# conveyor-pcb.net
KiCad netlist of a schematic drawn in EAGLE
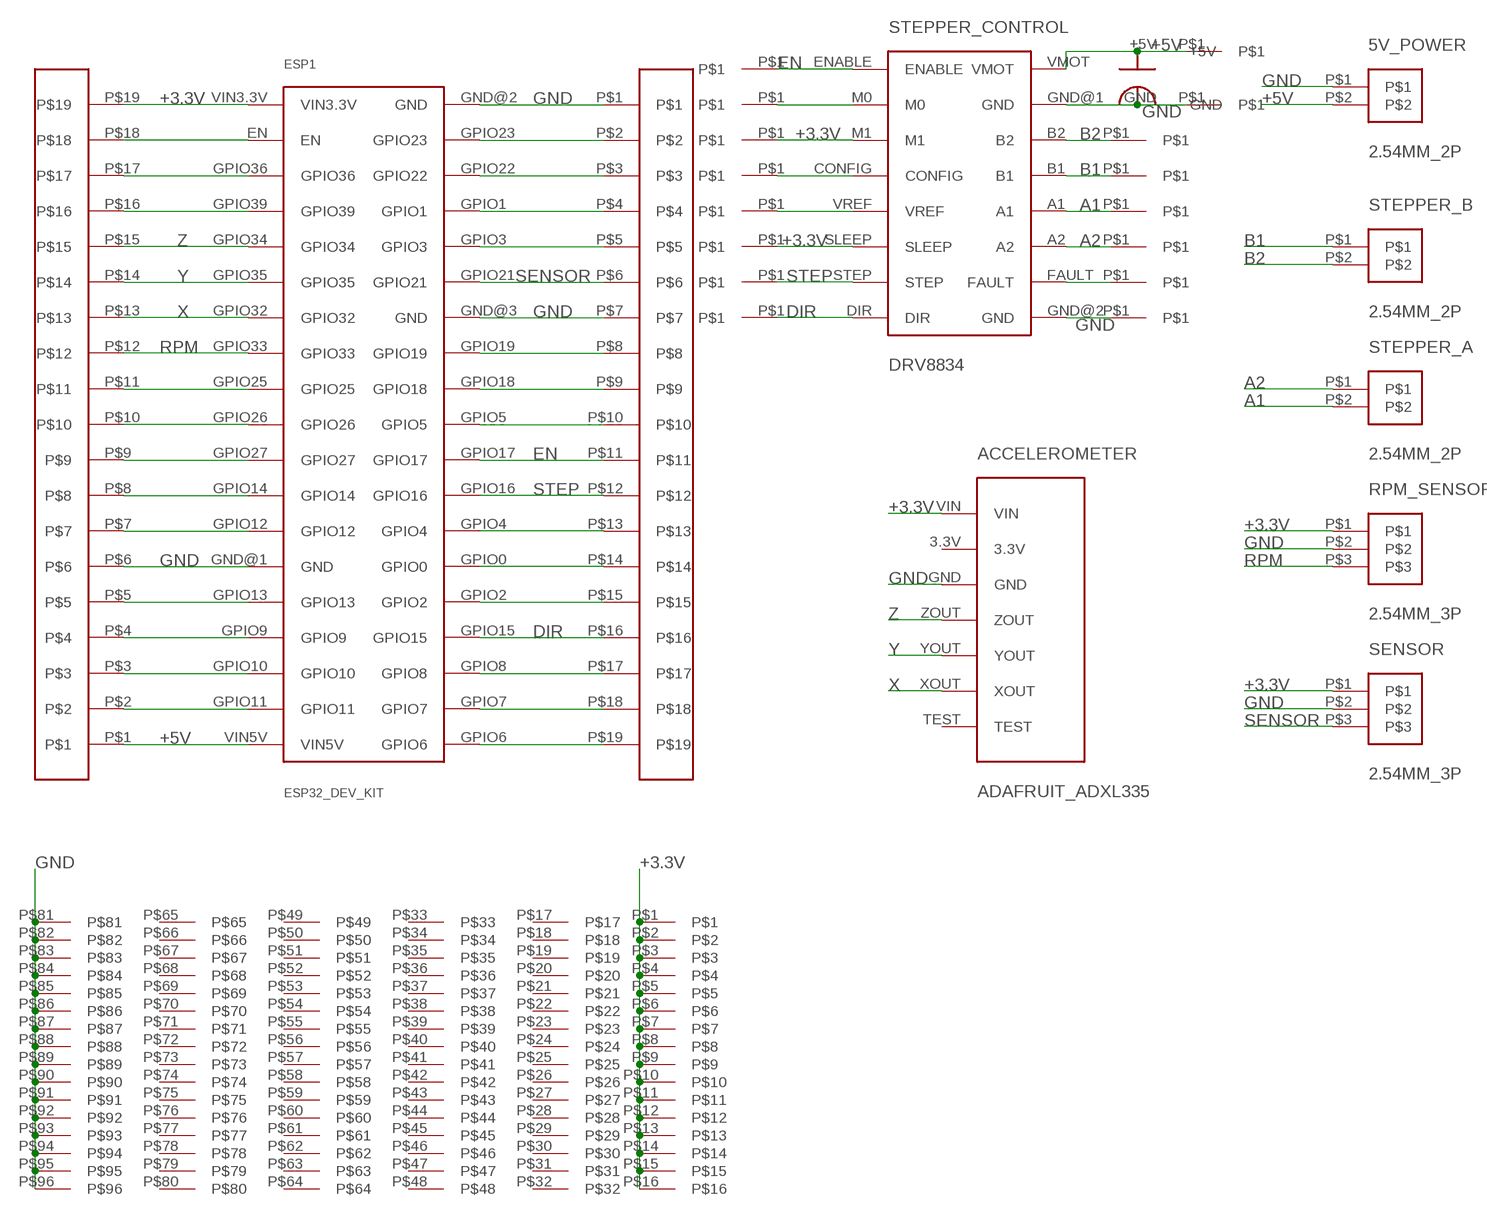
[diagram p0: schematic, sheet 1]

(export (version "E")
  (design (tool "Eeschema 10.0.6"))
  (components
    (comp (ref "5V_POWER")
      (value "2.54MM_2P")
      (footprint "eagle-import:2.54MM_2P")
      (libsource (lib "eagle-import") (part "2.54MM_2P"))
    )
    (comp (ref "ACCELEROMETER")
      (value "ADAFRUIT_ADXL335")
      (footprint "eagle-import:ADAFRUIT_ADXL335")
      (libsource (lib "eagle-import") (part "ADAFRUIT_ADXL335"))
    )
    (comp (ref "ESP1")
      (value "ESP32_DEV_KIT")
      (footprint "eagle-import:ESP32_DEV_KIT")
      (libsource (lib "eagle-import") (part "ESP32_DEV_KIT"))
    )
    (comp (ref "RPM_SENSOR")
      (value "2.54MM_3P")
      (footprint "eagle-import:2.54MM_3P")
      (libsource (lib "eagle-import") (part "2.54MM_3P"))
    )
    (comp (ref "SENSOR")
      (value "2.54MM_3P")
      (footprint "eagle-import:2.54MM_3P")
      (libsource (lib "eagle-import") (part "2.54MM_3P"))
    )
    (comp (ref "STEPPER_A")
      (value "2.54MM_2P")
      (footprint "eagle-import:2.54MM_2P")
      (libsource (lib "eagle-import") (part "2.54MM_2P"))
    )
    (comp (ref "STEPPER_B")
      (value "2.54MM_2P")
      (footprint "eagle-import:2.54MM_2P")
      (libsource (lib "eagle-import") (part "2.54MM_2P"))
    )
    (comp (ref "STEPPER_CONTROL")
      (value "DRV8834")
      (footprint "eagle-import:DRV8834")
      (libsource (lib "eagle-import") (part "DRV8834"))
    )
    (comp (ref "U$1")
      (value "19PINHEADER")
      (footprint "eagle-import:19PINHEADER")
      (libsource (lib "eagle-import") (part "19PINHEADER"))
    )
    (comp (ref "U$2")
      (value "19PINHEADER")
      (footprint "eagle-import:19PINHEADER")
      (libsource (lib "eagle-import") (part "19PINHEADER"))
    )
    (comp (ref "U$3")
      (value "PERFBOARD_CONVEYOR")
      (footprint "eagle-import:PERFBOARD_CONVEYOR")
      (libsource (lib "eagle-import") (part "PERFBOARD_CONVEYOR"))
    )
    (comp (ref "U$4")
      (value "1PIN_HEADER")
      (footprint "eagle-import:1PIN_HEADER")
      (libsource (lib "eagle-import") (part "1PIN_HEADER"))
    )
    (comp (ref "U$5")
      (value "1PIN_HEADER")
      (footprint "eagle-import:1PIN_HEADER")
      (libsource (lib "eagle-import") (part "1PIN_HEADER"))
    )
    (comp (ref "U$6")
      (value "1PIN_HEADER")
      (footprint "eagle-import:1PIN_HEADER")
      (libsource (lib "eagle-import") (part "1PIN_HEADER"))
    )
    (comp (ref "U$7")
      (value "1PIN_HEADER")
      (footprint "eagle-import:1PIN_HEADER")
      (libsource (lib "eagle-import") (part "1PIN_HEADER"))
    )
    (comp (ref "U$8")
      (value "1PIN_HEADER")
      (footprint "eagle-import:1PIN_HEADER")
      (libsource (lib "eagle-import") (part "1PIN_HEADER"))
    )
    (comp (ref "U$9")
      (value "1PIN_HEADER")
      (footprint "eagle-import:1PIN_HEADER")
      (libsource (lib "eagle-import") (part "1PIN_HEADER"))
    )
    (comp (ref "U$10")
      (value "1PIN_HEADER")
      (footprint "eagle-import:1PIN_HEADER")
      (libsource (lib "eagle-import") (part "1PIN_HEADER"))
    )
    (comp (ref "U$11")
      (value "1PIN_HEADER")
      (footprint "eagle-import:1PIN_HEADER")
      (libsource (lib "eagle-import") (part "1PIN_HEADER"))
    )
    (comp (ref "U$12")
      (value "1PIN_HEADER")
      (footprint "eagle-import:1PIN_HEADER")
      (libsource (lib "eagle-import") (part "1PIN_HEADER"))
    )
    (comp (ref "U$13")
      (value "1PIN_HEADER")
      (footprint "eagle-import:1PIN_HEADER")
      (libsource (lib "eagle-import") (part "1PIN_HEADER"))
    )
    (comp (ref "U$14")
      (value "1PIN_HEADER")
      (footprint "eagle-import:1PIN_HEADER")
      (libsource (lib "eagle-import") (part "1PIN_HEADER"))
    )
    (comp (ref "U$15")
      (value "1PIN_HEADER")
      (footprint "eagle-import:1PIN_HEADER")
      (libsource (lib "eagle-import") (part "1PIN_HEADER"))
    )
    (comp (ref "U$16")
      (value "1PIN_HEADER")
      (footprint "eagle-import:1PIN_HEADER")
      (libsource (lib "eagle-import") (part "1PIN_HEADER"))
    )
    (comp (ref "U$17")
      (value "1PIN_HEADER")
      (footprint "eagle-import:1PIN_HEADER")
      (libsource (lib "eagle-import") (part "1PIN_HEADER"))
    )
    (comp (ref "U$18")
      (value "1PIN_HEADER")
      (footprint "eagle-import:1PIN_HEADER")
      (libsource (lib "eagle-import") (part "1PIN_HEADER"))
    )
    (comp (ref "U$19")
      (value "1PIN_HEADER")
      (footprint "eagle-import:1PIN_HEADER")
      (libsource (lib "eagle-import") (part "1PIN_HEADER"))
    )
    (comp (ref "U$20")
      (value "CAP_100UF")
      (footprint "eagle-import:CAP_100UF")
      (libsource (lib "eagle-import") (part "CAP_100UF"))
    )
  )
  (nets
    (net (code "1") (name "/+3.3V") (class "Default")
      (node (ref "ACCELEROMETER") (pin "VIN") (pinfunction "VIN_VIN") (pintype "bidirectional"))
      (node (ref "ESP1") (pin "VIN3.3V") (pinfunction "VIN3.3V_VIN3.3V") (pintype "bidirectional"))
      (node (ref "RPM_SENSOR") (pin "P$1") (pinfunction "P$1_P$1") (pintype "bidirectional"))
      (node (ref "SENSOR") (pin "P$1") (pinfunction "P$1_P$1") (pintype "bidirectional"))
      (node (ref "STEPPER_CONTROL") (pin "M1") (pinfunction "M1_M1") (pintype "bidirectional"))
      (node (ref "STEPPER_CONTROL") (pin "SLEEP") (pinfunction "SLEEP_SLEEP") (pintype "bidirectional"))
      (node (ref "U$2") (pin "P$19") (pinfunction "P$19_P$19") (pintype "bidirectional"))
      (node (ref "U$3") (pin "P$1") (pinfunction "P$1_P$1") (pintype "bidirectional"))
      (node (ref "U$3") (pin "P$10") (pinfunction "P$10_P$10") (pintype "bidirectional"))
      (node (ref "U$3") (pin "P$11") (pinfunction "P$11_P$11") (pintype "bidirectional"))
      (node (ref "U$3") (pin "P$12") (pinfunction "P$12_P$12") (pintype "bidirectional"))
      (node (ref "U$3") (pin "P$13") (pinfunction "P$13_P$13") (pintype "bidirectional"))
      (node (ref "U$3") (pin "P$14") (pinfunction "P$14_P$14") (pintype "bidirectional"))
      (node (ref "U$3") (pin "P$15") (pinfunction "P$15_P$15") (pintype "bidirectional"))
      (node (ref "U$3") (pin "P$16") (pinfunction "P$16_P$16") (pintype "bidirectional"))
      (node (ref "U$3") (pin "P$2") (pinfunction "P$2_P$2") (pintype "bidirectional"))
      (node (ref "U$3") (pin "P$3") (pinfunction "P$3_P$3") (pintype "bidirectional"))
      (node (ref "U$3") (pin "P$4") (pinfunction "P$4_P$4") (pintype "bidirectional"))
      (node (ref "U$3") (pin "P$5") (pinfunction "P$5_P$5") (pintype "bidirectional"))
      (node (ref "U$3") (pin "P$6") (pinfunction "P$6_P$6") (pintype "bidirectional"))
      (node (ref "U$3") (pin "P$7") (pinfunction "P$7_P$7") (pintype "bidirectional"))
      (node (ref "U$3") (pin "P$8") (pinfunction "P$8_P$8") (pintype "bidirectional"))
      (node (ref "U$3") (pin "P$9") (pinfunction "P$9_P$9") (pintype "bidirectional"))
      (node (ref "U$6") (pin "P$1") (pinfunction "P$1_P$1") (pintype "bidirectional"))
      (node (ref "U$9") (pin "P$1") (pinfunction "P$1_P$1") (pintype "bidirectional"))
    )
    (net (code "2") (name "/+5V") (class "Default")
      (node (ref "5V_POWER") (pin "P$2") (pinfunction "P$2_P$2") (pintype "bidirectional"))
      (node (ref "ESP1") (pin "VIN5V") (pinfunction "VIN5V_VIN5V") (pintype "bidirectional"))
      (node (ref "STEPPER_CONTROL") (pin "VMOT") (pinfunction "VMOT_VMOT") (pintype "bidirectional"))
      (node (ref "U$19") (pin "P$1") (pinfunction "P$1_P$1") (pintype "bidirectional"))
      (node (ref "U$2") (pin "P$1") (pinfunction "P$1_P$1") (pintype "bidirectional"))
      (node (ref "U$20") (pin "+5V") (pinfunction "+5V_+5V") (pintype "bidirectional"))
    )
    (net (code "3") (name "/A1") (class "Default")
      (node (ref "STEPPER_A") (pin "P$2") (pinfunction "P$2_P$2") (pintype "bidirectional"))
      (node (ref "STEPPER_CONTROL") (pin "A1") (pinfunction "A1_A1") (pintype "bidirectional"))
      (node (ref "U$15") (pin "P$1") (pinfunction "P$1_P$1") (pintype "bidirectional"))
    )
    (net (code "4") (name "/A2") (class "Default")
      (node (ref "STEPPER_A") (pin "P$1") (pinfunction "P$1_P$1") (pintype "bidirectional"))
      (node (ref "STEPPER_CONTROL") (pin "A2") (pinfunction "A2_A2") (pintype "bidirectional"))
      (node (ref "U$14") (pin "P$1") (pinfunction "P$1_P$1") (pintype "bidirectional"))
    )
    (net (code "5") (name "/B1") (class "Default")
      (node (ref "STEPPER_B") (pin "P$1") (pinfunction "P$1_P$1") (pintype "bidirectional"))
      (node (ref "STEPPER_CONTROL") (pin "B1") (pinfunction "B1_B1") (pintype "bidirectional"))
      (node (ref "U$16") (pin "P$1") (pinfunction "P$1_P$1") (pintype "bidirectional"))
    )
    (net (code "6") (name "/B2") (class "Default")
      (node (ref "STEPPER_B") (pin "P$2") (pinfunction "P$2_P$2") (pintype "bidirectional"))
      (node (ref "STEPPER_CONTROL") (pin "B2") (pinfunction "B2_B2") (pintype "bidirectional"))
      (node (ref "U$17") (pin "P$1") (pinfunction "P$1_P$1") (pintype "bidirectional"))
    )
    (net (code "7") (name "/DIR") (class "Default")
      (node (ref "ESP1") (pin "GPIO15") (pinfunction "GPIO15_GPIO15") (pintype "bidirectional"))
      (node (ref "STEPPER_CONTROL") (pin "DIR") (pinfunction "DIR_DIR") (pintype "bidirectional"))
      (node (ref "U$1") (pin "P$16") (pinfunction "P$16_P$16") (pintype "bidirectional"))
      (node (ref "U$11") (pin "P$1") (pinfunction "P$1_P$1") (pintype "bidirectional"))
    )
    (net (code "8") (name "/EN") (class "Default")
      (node (ref "ESP1") (pin "GPIO17") (pinfunction "GPIO17_GPIO17") (pintype "bidirectional"))
      (node (ref "STEPPER_CONTROL") (pin "ENABLE") (pinfunction "ENABLE_ENABLE") (pintype "bidirectional"))
      (node (ref "U$1") (pin "P$11") (pinfunction "P$11_P$11") (pintype "bidirectional"))
      (node (ref "U$4") (pin "P$1") (pinfunction "P$1_P$1") (pintype "bidirectional"))
    )
    (net (code "9") (name "/GND") (class "Default")
      (node (ref "5V_POWER") (pin "P$1") (pinfunction "P$1_P$1") (pintype "bidirectional"))
      (node (ref "ACCELEROMETER") (pin "GND") (pinfunction "GND_GND") (pintype "bidirectional"))
      (node (ref "ESP1") (pin "GND@1") (pinfunction "GND_GND@1") (pintype "bidirectional"))
      (node (ref "ESP1") (pin "GND@2") (pinfunction "GND_GND@2") (pintype "bidirectional"))
      (node (ref "ESP1") (pin "GND@3") (pinfunction "GND_GND@3") (pintype "bidirectional"))
      (node (ref "RPM_SENSOR") (pin "P$2") (pinfunction "P$2_P$2") (pintype "bidirectional"))
      (node (ref "SENSOR") (pin "P$2") (pinfunction "P$2_P$2") (pintype "bidirectional"))
      (node (ref "STEPPER_CONTROL") (pin "GND@1") (pinfunction "GND_GND@1") (pintype "bidirectional"))
      (node (ref "STEPPER_CONTROL") (pin "GND@2") (pinfunction "GND_GND@2") (pintype "bidirectional"))
      (node (ref "U$1") (pin "P$1") (pinfunction "P$1_P$1") (pintype "bidirectional"))
      (node (ref "U$1") (pin "P$7") (pinfunction "P$7_P$7") (pintype "bidirectional"))
      (node (ref "U$12") (pin "P$1") (pinfunction "P$1_P$1") (pintype "bidirectional"))
      (node (ref "U$18") (pin "P$1") (pinfunction "P$1_P$1") (pintype "bidirectional"))
      (node (ref "U$2") (pin "P$6") (pinfunction "P$6_P$6") (pintype "bidirectional"))
      (node (ref "U$20") (pin "GND") (pinfunction "GND_GND") (pintype "bidirectional"))
      (node (ref "U$3") (pin "P$81") (pinfunction "P$81_P$81") (pintype "bidirectional"))
      (node (ref "U$3") (pin "P$82") (pinfunction "P$82_P$82") (pintype "bidirectional"))
      (node (ref "U$3") (pin "P$83") (pinfunction "P$83_P$83") (pintype "bidirectional"))
      (node (ref "U$3") (pin "P$84") (pinfunction "P$84_P$84") (pintype "bidirectional"))
      (node (ref "U$3") (pin "P$85") (pinfunction "P$85_P$85") (pintype "bidirectional"))
      (node (ref "U$3") (pin "P$86") (pinfunction "P$86_P$86") (pintype "bidirectional"))
      (node (ref "U$3") (pin "P$87") (pinfunction "P$87_P$87") (pintype "bidirectional"))
      (node (ref "U$3") (pin "P$88") (pinfunction "P$88_P$88") (pintype "bidirectional"))
      (node (ref "U$3") (pin "P$89") (pinfunction "P$89_P$89") (pintype "bidirectional"))
      (node (ref "U$3") (pin "P$90") (pinfunction "P$90_P$90") (pintype "bidirectional"))
      (node (ref "U$3") (pin "P$91") (pinfunction "P$91_P$91") (pintype "bidirectional"))
      (node (ref "U$3") (pin "P$92") (pinfunction "P$92_P$92") (pintype "bidirectional"))
      (node (ref "U$3") (pin "P$93") (pinfunction "P$93_P$93") (pintype "bidirectional"))
      (node (ref "U$3") (pin "P$94") (pinfunction "P$94_P$94") (pintype "bidirectional"))
      (node (ref "U$3") (pin "P$95") (pinfunction "P$95_P$95") (pintype "bidirectional"))
      (node (ref "U$3") (pin "P$96") (pinfunction "P$96_P$96") (pintype "bidirectional"))
    )
    (net (code "10") (name "/RPM") (class "Default")
      (node (ref "ESP1") (pin "GPIO33") (pinfunction "GPIO33_GPIO33") (pintype "bidirectional"))
      (node (ref "RPM_SENSOR") (pin "P$3") (pinfunction "P$3_P$3") (pintype "bidirectional"))
      (node (ref "U$2") (pin "P$12") (pinfunction "P$12_P$12") (pintype "bidirectional"))
    )
    (net (code "11") (name "/SENSOR") (class "Default")
      (node (ref "ESP1") (pin "GPIO21") (pinfunction "GPIO21_GPIO21") (pintype "bidirectional"))
      (node (ref "SENSOR") (pin "P$3") (pinfunction "P$3_P$3") (pintype "bidirectional"))
      (node (ref "U$1") (pin "P$6") (pinfunction "P$6_P$6") (pintype "bidirectional"))
    )
    (net (code "12") (name "/STEP") (class "Default")
      (node (ref "ESP1") (pin "GPIO16") (pinfunction "GPIO16_GPIO16") (pintype "bidirectional"))
      (node (ref "STEPPER_CONTROL") (pin "STEP") (pinfunction "STEP_STEP") (pintype "bidirectional"))
      (node (ref "U$1") (pin "P$12") (pinfunction "P$12_P$12") (pintype "bidirectional"))
      (node (ref "U$10") (pin "P$1") (pinfunction "P$1_P$1") (pintype "bidirectional"))
    )
    (net (code "13") (name "/X") (class "Default")
      (node (ref "ACCELEROMETER") (pin "XOUT") (pinfunction "XOUT_XOUT") (pintype "bidirectional"))
      (node (ref "ESP1") (pin "GPIO32") (pinfunction "GPIO32_GPIO32") (pintype "bidirectional"))
      (node (ref "U$2") (pin "P$13") (pinfunction "P$13_P$13") (pintype "bidirectional"))
    )
    (net (code "14") (name "/Y") (class "Default")
      (node (ref "ACCELEROMETER") (pin "YOUT") (pinfunction "YOUT_YOUT") (pintype "bidirectional"))
      (node (ref "ESP1") (pin "GPIO35") (pinfunction "GPIO35_GPIO35") (pintype "bidirectional"))
      (node (ref "U$2") (pin "P$14") (pinfunction "P$14_P$14") (pintype "bidirectional"))
    )
    (net (code "15") (name "/Z") (class "Default")
      (node (ref "ACCELEROMETER") (pin "ZOUT") (pinfunction "ZOUT_ZOUT") (pintype "bidirectional"))
      (node (ref "ESP1") (pin "GPIO34") (pinfunction "GPIO34_GPIO34") (pintype "bidirectional"))
      (node (ref "U$2") (pin "P$15") (pinfunction "P$15_P$15") (pintype "bidirectional"))
    )
    (net (code "16") (name "Net-(ESP1-PadEN)") (class "Default")
      (node (ref "ESP1") (pin "EN") (pinfunction "EN_EN") (pintype "bidirectional"))
      (node (ref "U$2") (pin "P$18") (pinfunction "P$18_P$18") (pintype "bidirectional"))
    )
    (net (code "17") (name "Net-(ESP1-PadGPIO0)") (class "Default")
      (node (ref "ESP1") (pin "GPIO0") (pinfunction "GPIO0_GPIO0") (pintype "bidirectional"))
      (node (ref "U$1") (pin "P$14") (pinfunction "P$14_P$14") (pintype "bidirectional"))
    )
    (net (code "18") (name "Net-(ESP1-PadGPIO1)") (class "Default")
      (node (ref "ESP1") (pin "GPIO1") (pinfunction "GPIO1_GPIO1") (pintype "bidirectional"))
      (node (ref "U$1") (pin "P$4") (pinfunction "P$4_P$4") (pintype "bidirectional"))
    )
    (net (code "19") (name "Net-(ESP1-PadGPIO2)") (class "Default")
      (node (ref "ESP1") (pin "GPIO2") (pinfunction "GPIO2_GPIO2") (pintype "bidirectional"))
      (node (ref "U$1") (pin "P$15") (pinfunction "P$15_P$15") (pintype "bidirectional"))
    )
    (net (code "20") (name "Net-(ESP1-PadGPIO3)") (class "Default")
      (node (ref "ESP1") (pin "GPIO3") (pinfunction "GPIO3_GPIO3") (pintype "bidirectional"))
      (node (ref "U$1") (pin "P$5") (pinfunction "P$5_P$5") (pintype "bidirectional"))
    )
    (net (code "21") (name "Net-(ESP1-PadGPIO4)") (class "Default")
      (node (ref "ESP1") (pin "GPIO4") (pinfunction "GPIO4_GPIO4") (pintype "bidirectional"))
      (node (ref "U$1") (pin "P$13") (pinfunction "P$13_P$13") (pintype "bidirectional"))
    )
    (net (code "22") (name "Net-(ESP1-PadGPIO5)") (class "Default")
      (node (ref "ESP1") (pin "GPIO5") (pinfunction "GPIO5_GPIO5") (pintype "bidirectional"))
      (node (ref "U$1") (pin "P$10") (pinfunction "P$10_P$10") (pintype "bidirectional"))
    )
    (net (code "23") (name "Net-(ESP1-PadGPIO6)") (class "Default")
      (node (ref "ESP1") (pin "GPIO6") (pinfunction "GPIO6_GPIO6") (pintype "bidirectional"))
      (node (ref "U$1") (pin "P$19") (pinfunction "P$19_P$19") (pintype "bidirectional"))
    )
    (net (code "24") (name "Net-(ESP1-PadGPIO7)") (class "Default")
      (node (ref "ESP1") (pin "GPIO7") (pinfunction "GPIO7_GPIO7") (pintype "bidirectional"))
      (node (ref "U$1") (pin "P$18") (pinfunction "P$18_P$18") (pintype "bidirectional"))
    )
    (net (code "25") (name "Net-(ESP1-PadGPIO8)") (class "Default")
      (node (ref "ESP1") (pin "GPIO8") (pinfunction "GPIO8_GPIO8") (pintype "bidirectional"))
      (node (ref "U$1") (pin "P$17") (pinfunction "P$17_P$17") (pintype "bidirectional"))
    )
    (net (code "26") (name "Net-(ESP1-PadGPIO9)") (class "Default")
      (node (ref "ESP1") (pin "GPIO9") (pinfunction "GPIO9_GPIO9") (pintype "bidirectional"))
      (node (ref "U$2") (pin "P$4") (pinfunction "P$4_P$4") (pintype "bidirectional"))
    )
    (net (code "27") (name "Net-(ESP1-PadGPIO10)") (class "Default")
      (node (ref "ESP1") (pin "GPIO10") (pinfunction "GPIO10_GPIO10") (pintype "bidirectional"))
      (node (ref "U$2") (pin "P$3") (pinfunction "P$3_P$3") (pintype "bidirectional"))
    )
    (net (code "28") (name "Net-(ESP1-PadGPIO11)") (class "Default")
      (node (ref "ESP1") (pin "GPIO11") (pinfunction "GPIO11_GPIO11") (pintype "bidirectional"))
      (node (ref "U$2") (pin "P$2") (pinfunction "P$2_P$2") (pintype "bidirectional"))
    )
    (net (code "29") (name "Net-(ESP1-PadGPIO12)") (class "Default")
      (node (ref "ESP1") (pin "GPIO12") (pinfunction "GPIO12_GPIO12") (pintype "bidirectional"))
      (node (ref "U$2") (pin "P$7") (pinfunction "P$7_P$7") (pintype "bidirectional"))
    )
    (net (code "30") (name "Net-(ESP1-PadGPIO13)") (class "Default")
      (node (ref "ESP1") (pin "GPIO13") (pinfunction "GPIO13_GPIO13") (pintype "bidirectional"))
      (node (ref "U$2") (pin "P$5") (pinfunction "P$5_P$5") (pintype "bidirectional"))
    )
    (net (code "31") (name "Net-(ESP1-PadGPIO14)") (class "Default")
      (node (ref "ESP1") (pin "GPIO14") (pinfunction "GPIO14_GPIO14") (pintype "bidirectional"))
      (node (ref "U$2") (pin "P$8") (pinfunction "P$8_P$8") (pintype "bidirectional"))
    )
    (net (code "32") (name "Net-(ESP1-PadGPIO18)") (class "Default")
      (node (ref "ESP1") (pin "GPIO18") (pinfunction "GPIO18_GPIO18") (pintype "bidirectional"))
      (node (ref "U$1") (pin "P$9") (pinfunction "P$9_P$9") (pintype "bidirectional"))
    )
    (net (code "33") (name "Net-(ESP1-PadGPIO19)") (class "Default")
      (node (ref "ESP1") (pin "GPIO19") (pinfunction "GPIO19_GPIO19") (pintype "bidirectional"))
      (node (ref "U$1") (pin "P$8") (pinfunction "P$8_P$8") (pintype "bidirectional"))
    )
    (net (code "34") (name "Net-(ESP1-PadGPIO22)") (class "Default")
      (node (ref "ESP1") (pin "GPIO22") (pinfunction "GPIO22_GPIO22") (pintype "bidirectional"))
      (node (ref "U$1") (pin "P$3") (pinfunction "P$3_P$3") (pintype "bidirectional"))
    )
    (net (code "35") (name "Net-(ESP1-PadGPIO23)") (class "Default")
      (node (ref "ESP1") (pin "GPIO23") (pinfunction "GPIO23_GPIO23") (pintype "bidirectional"))
      (node (ref "U$1") (pin "P$2") (pinfunction "P$2_P$2") (pintype "bidirectional"))
    )
    (net (code "36") (name "Net-(ESP1-PadGPIO25)") (class "Default")
      (node (ref "ESP1") (pin "GPIO25") (pinfunction "GPIO25_GPIO25") (pintype "bidirectional"))
      (node (ref "U$2") (pin "P$11") (pinfunction "P$11_P$11") (pintype "bidirectional"))
    )
    (net (code "37") (name "Net-(ESP1-PadGPIO26)") (class "Default")
      (node (ref "ESP1") (pin "GPIO26") (pinfunction "GPIO26_GPIO26") (pintype "bidirectional"))
      (node (ref "U$2") (pin "P$10") (pinfunction "P$10_P$10") (pintype "bidirectional"))
    )
    (net (code "38") (name "Net-(ESP1-PadGPIO27)") (class "Default")
      (node (ref "ESP1") (pin "GPIO27") (pinfunction "GPIO27_GPIO27") (pintype "bidirectional"))
      (node (ref "U$2") (pin "P$9") (pinfunction "P$9_P$9") (pintype "bidirectional"))
    )
    (net (code "39") (name "Net-(ESP1-PadGPIO36)") (class "Default")
      (node (ref "ESP1") (pin "GPIO36") (pinfunction "GPIO36_GPIO36") (pintype "bidirectional"))
      (node (ref "U$2") (pin "P$17") (pinfunction "P$17_P$17") (pintype "bidirectional"))
    )
    (net (code "40") (name "Net-(ESP1-PadGPIO39)") (class "Default")
      (node (ref "ESP1") (pin "GPIO39") (pinfunction "GPIO39_GPIO39") (pintype "bidirectional"))
      (node (ref "U$2") (pin "P$16") (pinfunction "P$16_P$16") (pintype "bidirectional"))
    )
    (net (code "41") (name "Net-(STEPPER_CONTROL-PadCONFIG)") (class "Default")
      (node (ref "STEPPER_CONTROL") (pin "CONFIG") (pinfunction "CONFIG_CONFIG") (pintype "bidirectional"))
      (node (ref "U$7") (pin "P$1") (pinfunction "P$1_P$1") (pintype "bidirectional"))
    )
    (net (code "42") (name "Net-(STEPPER_CONTROL-PadFAULT)") (class "Default")
      (node (ref "STEPPER_CONTROL") (pin "FAULT") (pinfunction "FAULT_FAULT") (pintype "bidirectional"))
      (node (ref "U$13") (pin "P$1") (pinfunction "P$1_P$1") (pintype "bidirectional"))
    )
    (net (code "43") (name "Net-(STEPPER_CONTROL-PadM0)") (class "Default")
      (node (ref "STEPPER_CONTROL") (pin "M0") (pinfunction "M0_M0") (pintype "bidirectional"))
      (node (ref "U$5") (pin "P$1") (pinfunction "P$1_P$1") (pintype "bidirectional"))
    )
    (net (code "44") (name "Net-(STEPPER_CONTROL-PadVREF)") (class "Default")
      (node (ref "STEPPER_CONTROL") (pin "VREF") (pinfunction "VREF_VREF") (pintype "bidirectional"))
      (node (ref "U$8") (pin "P$1") (pinfunction "P$1_P$1") (pintype "bidirectional"))
    )
    (net (code "45") (name "unconnected-(ACCELEROMETER-Pad3.3V)") (class "Default")
      (node (ref "ACCELEROMETER") (pin "3.3V") (pinfunction "3.3V_3.3V") (pintype "bidirectional"))
    )
    (net (code "46") (name "unconnected-(ACCELEROMETER-PadTEST)") (class "Default")
      (node (ref "ACCELEROMETER") (pin "TEST") (pinfunction "TEST_TEST") (pintype "bidirectional"))
    )
    (net (code "47") (name "unconnected-(U$3-PadP$17)") (class "Default")
      (node (ref "U$3") (pin "P$17") (pinfunction "P$17_P$17") (pintype "bidirectional"))
    )
    (net (code "48") (name "unconnected-(U$3-PadP$18)") (class "Default")
      (node (ref "U$3") (pin "P$18") (pinfunction "P$18_P$18") (pintype "bidirectional"))
    )
    (net (code "49") (name "unconnected-(U$3-PadP$19)") (class "Default")
      (node (ref "U$3") (pin "P$19") (pinfunction "P$19_P$19") (pintype "bidirectional"))
    )
    (net (code "50") (name "unconnected-(U$3-PadP$20)") (class "Default")
      (node (ref "U$3") (pin "P$20") (pinfunction "P$20_P$20") (pintype "bidirectional"))
    )
    (net (code "51") (name "unconnected-(U$3-PadP$21)") (class "Default")
      (node (ref "U$3") (pin "P$21") (pinfunction "P$21_P$21") (pintype "bidirectional"))
    )
    (net (code "52") (name "unconnected-(U$3-PadP$22)") (class "Default")
      (node (ref "U$3") (pin "P$22") (pinfunction "P$22_P$22") (pintype "bidirectional"))
    )
    (net (code "53") (name "unconnected-(U$3-PadP$23)") (class "Default")
      (node (ref "U$3") (pin "P$23") (pinfunction "P$23_P$23") (pintype "bidirectional"))
    )
    (net (code "54") (name "unconnected-(U$3-PadP$24)") (class "Default")
      (node (ref "U$3") (pin "P$24") (pinfunction "P$24_P$24") (pintype "bidirectional"))
    )
    (net (code "55") (name "unconnected-(U$3-PadP$25)") (class "Default")
      (node (ref "U$3") (pin "P$25") (pinfunction "P$25_P$25") (pintype "bidirectional"))
    )
    (net (code "56") (name "unconnected-(U$3-PadP$26)") (class "Default")
      (node (ref "U$3") (pin "P$26") (pinfunction "P$26_P$26") (pintype "bidirectional"))
    )
    (net (code "57") (name "unconnected-(U$3-PadP$27)") (class "Default")
      (node (ref "U$3") (pin "P$27") (pinfunction "P$27_P$27") (pintype "bidirectional"))
    )
    (net (code "58") (name "unconnected-(U$3-PadP$28)") (class "Default")
      (node (ref "U$3") (pin "P$28") (pinfunction "P$28_P$28") (pintype "bidirectional"))
    )
    (net (code "59") (name "unconnected-(U$3-PadP$29)") (class "Default")
      (node (ref "U$3") (pin "P$29") (pinfunction "P$29_P$29") (pintype "bidirectional"))
    )
    (net (code "60") (name "unconnected-(U$3-PadP$30)") (class "Default")
      (node (ref "U$3") (pin "P$30") (pinfunction "P$30_P$30") (pintype "bidirectional"))
    )
    (net (code "61") (name "unconnected-(U$3-PadP$31)") (class "Default")
      (node (ref "U$3") (pin "P$31") (pinfunction "P$31_P$31") (pintype "bidirectional"))
    )
    (net (code "62") (name "unconnected-(U$3-PadP$32)") (class "Default")
      (node (ref "U$3") (pin "P$32") (pinfunction "P$32_P$32") (pintype "bidirectional"))
    )
    (net (code "63") (name "unconnected-(U$3-PadP$33)") (class "Default")
      (node (ref "U$3") (pin "P$33") (pinfunction "P$33_P$33") (pintype "bidirectional"))
    )
    (net (code "64") (name "unconnected-(U$3-PadP$34)") (class "Default")
      (node (ref "U$3") (pin "P$34") (pinfunction "P$34_P$34") (pintype "bidirectional"))
    )
    (net (code "65") (name "unconnected-(U$3-PadP$35)") (class "Default")
      (node (ref "U$3") (pin "P$35") (pinfunction "P$35_P$35") (pintype "bidirectional"))
    )
    (net (code "66") (name "unconnected-(U$3-PadP$36)") (class "Default")
      (node (ref "U$3") (pin "P$36") (pinfunction "P$36_P$36") (pintype "bidirectional"))
    )
    (net (code "67") (name "unconnected-(U$3-PadP$37)") (class "Default")
      (node (ref "U$3") (pin "P$37") (pinfunction "P$37_P$37") (pintype "bidirectional"))
    )
    (net (code "68") (name "unconnected-(U$3-PadP$38)") (class "Default")
      (node (ref "U$3") (pin "P$38") (pinfunction "P$38_P$38") (pintype "bidirectional"))
    )
    (net (code "69") (name "unconnected-(U$3-PadP$39)") (class "Default")
      (node (ref "U$3") (pin "P$39") (pinfunction "P$39_P$39") (pintype "bidirectional"))
    )
    (net (code "70") (name "unconnected-(U$3-PadP$40)") (class "Default")
      (node (ref "U$3") (pin "P$40") (pinfunction "P$40_P$40") (pintype "bidirectional"))
    )
    (net (code "71") (name "unconnected-(U$3-PadP$41)") (class "Default")
      (node (ref "U$3") (pin "P$41") (pinfunction "P$41_P$41") (pintype "bidirectional"))
    )
    (net (code "72") (name "unconnected-(U$3-PadP$42)") (class "Default")
      (node (ref "U$3") (pin "P$42") (pinfunction "P$42_P$42") (pintype "bidirectional"))
    )
    (net (code "73") (name "unconnected-(U$3-PadP$43)") (class "Default")
      (node (ref "U$3") (pin "P$43") (pinfunction "P$43_P$43") (pintype "bidirectional"))
    )
    (net (code "74") (name "unconnected-(U$3-PadP$44)") (class "Default")
      (node (ref "U$3") (pin "P$44") (pinfunction "P$44_P$44") (pintype "bidirectional"))
    )
    (net (code "75") (name "unconnected-(U$3-PadP$45)") (class "Default")
      (node (ref "U$3") (pin "P$45") (pinfunction "P$45_P$45") (pintype "bidirectional"))
    )
    (net (code "76") (name "unconnected-(U$3-PadP$46)") (class "Default")
      (node (ref "U$3") (pin "P$46") (pinfunction "P$46_P$46") (pintype "bidirectional"))
    )
    (net (code "77") (name "unconnected-(U$3-PadP$47)") (class "Default")
      (node (ref "U$3") (pin "P$47") (pinfunction "P$47_P$47") (pintype "bidirectional"))
    )
    (net (code "78") (name "unconnected-(U$3-PadP$48)") (class "Default")
      (node (ref "U$3") (pin "P$48") (pinfunction "P$48_P$48") (pintype "bidirectional"))
    )
    (net (code "79") (name "unconnected-(U$3-PadP$49)") (class "Default")
      (node (ref "U$3") (pin "P$49") (pinfunction "P$49_P$49") (pintype "bidirectional"))
    )
    (net (code "80") (name "unconnected-(U$3-PadP$50)") (class "Default")
      (node (ref "U$3") (pin "P$50") (pinfunction "P$50_P$50") (pintype "bidirectional"))
    )
    (net (code "81") (name "unconnected-(U$3-PadP$51)") (class "Default")
      (node (ref "U$3") (pin "P$51") (pinfunction "P$51_P$51") (pintype "bidirectional"))
    )
    (net (code "82") (name "unconnected-(U$3-PadP$52)") (class "Default")
      (node (ref "U$3") (pin "P$52") (pinfunction "P$52_P$52") (pintype "bidirectional"))
    )
    (net (code "83") (name "unconnected-(U$3-PadP$53)") (class "Default")
      (node (ref "U$3") (pin "P$53") (pinfunction "P$53_P$53") (pintype "bidirectional"))
    )
    (net (code "84") (name "unconnected-(U$3-PadP$54)") (class "Default")
      (node (ref "U$3") (pin "P$54") (pinfunction "P$54_P$54") (pintype "bidirectional"))
    )
    (net (code "85") (name "unconnected-(U$3-PadP$55)") (class "Default")
      (node (ref "U$3") (pin "P$55") (pinfunction "P$55_P$55") (pintype "bidirectional"))
    )
    (net (code "86") (name "unconnected-(U$3-PadP$56)") (class "Default")
      (node (ref "U$3") (pin "P$56") (pinfunction "P$56_P$56") (pintype "bidirectional"))
    )
    (net (code "87") (name "unconnected-(U$3-PadP$57)") (class "Default")
      (node (ref "U$3") (pin "P$57") (pinfunction "P$57_P$57") (pintype "bidirectional"))
    )
    (net (code "88") (name "unconnected-(U$3-PadP$58)") (class "Default")
      (node (ref "U$3") (pin "P$58") (pinfunction "P$58_P$58") (pintype "bidirectional"))
    )
    (net (code "89") (name "unconnected-(U$3-PadP$59)") (class "Default")
      (node (ref "U$3") (pin "P$59") (pinfunction "P$59_P$59") (pintype "bidirectional"))
    )
    (net (code "90") (name "unconnected-(U$3-PadP$60)") (class "Default")
      (node (ref "U$3") (pin "P$60") (pinfunction "P$60_P$60") (pintype "bidirectional"))
    )
    (net (code "91") (name "unconnected-(U$3-PadP$61)") (class "Default")
      (node (ref "U$3") (pin "P$61") (pinfunction "P$61_P$61") (pintype "bidirectional"))
    )
    (net (code "92") (name "unconnected-(U$3-PadP$62)") (class "Default")
      (node (ref "U$3") (pin "P$62") (pinfunction "P$62_P$62") (pintype "bidirectional"))
    )
    (net (code "93") (name "unconnected-(U$3-PadP$63)") (class "Default")
      (node (ref "U$3") (pin "P$63") (pinfunction "P$63_P$63") (pintype "bidirectional"))
    )
    (net (code "94") (name "unconnected-(U$3-PadP$64)") (class "Default")
      (node (ref "U$3") (pin "P$64") (pinfunction "P$64_P$64") (pintype "bidirectional"))
    )
    (net (code "95") (name "unconnected-(U$3-PadP$65)") (class "Default")
      (node (ref "U$3") (pin "P$65") (pinfunction "P$65_P$65") (pintype "bidirectional"))
    )
    (net (code "96") (name "unconnected-(U$3-PadP$66)") (class "Default")
      (node (ref "U$3") (pin "P$66") (pinfunction "P$66_P$66") (pintype "bidirectional"))
    )
    (net (code "97") (name "unconnected-(U$3-PadP$67)") (class "Default")
      (node (ref "U$3") (pin "P$67") (pinfunction "P$67_P$67") (pintype "bidirectional"))
    )
    (net (code "98") (name "unconnected-(U$3-PadP$68)") (class "Default")
      (node (ref "U$3") (pin "P$68") (pinfunction "P$68_P$68") (pintype "bidirectional"))
    )
    (net (code "99") (name "unconnected-(U$3-PadP$69)") (class "Default")
      (node (ref "U$3") (pin "P$69") (pinfunction "P$69_P$69") (pintype "bidirectional"))
    )
    (net (code "100") (name "unconnected-(U$3-PadP$70)") (class "Default")
      (node (ref "U$3") (pin "P$70") (pinfunction "P$70_P$70") (pintype "bidirectional"))
    )
    (net (code "101") (name "unconnected-(U$3-PadP$71)") (class "Default")
      (node (ref "U$3") (pin "P$71") (pinfunction "P$71_P$71") (pintype "bidirectional"))
    )
    (net (code "102") (name "unconnected-(U$3-PadP$72)") (class "Default")
      (node (ref "U$3") (pin "P$72") (pinfunction "P$72_P$72") (pintype "bidirectional"))
    )
    (net (code "103") (name "unconnected-(U$3-PadP$73)") (class "Default")
      (node (ref "U$3") (pin "P$73") (pinfunction "P$73_P$73") (pintype "bidirectional"))
    )
    (net (code "104") (name "unconnected-(U$3-PadP$74)") (class "Default")
      (node (ref "U$3") (pin "P$74") (pinfunction "P$74_P$74") (pintype "bidirectional"))
    )
    (net (code "105") (name "unconnected-(U$3-PadP$75)") (class "Default")
      (node (ref "U$3") (pin "P$75") (pinfunction "P$75_P$75") (pintype "bidirectional"))
    )
    (net (code "106") (name "unconnected-(U$3-PadP$76)") (class "Default")
      (node (ref "U$3") (pin "P$76") (pinfunction "P$76_P$76") (pintype "bidirectional"))
    )
    (net (code "107") (name "unconnected-(U$3-PadP$77)") (class "Default")
      (node (ref "U$3") (pin "P$77") (pinfunction "P$77_P$77") (pintype "bidirectional"))
    )
    (net (code "108") (name "unconnected-(U$3-PadP$78)") (class "Default")
      (node (ref "U$3") (pin "P$78") (pinfunction "P$78_P$78") (pintype "bidirectional"))
    )
    (net (code "109") (name "unconnected-(U$3-PadP$79)") (class "Default")
      (node (ref "U$3") (pin "P$79") (pinfunction "P$79_P$79") (pintype "bidirectional"))
    )
    (net (code "110") (name "unconnected-(U$3-PadP$80)") (class "Default")
      (node (ref "U$3") (pin "P$80") (pinfunction "P$80_P$80") (pintype "bidirectional"))
    )
  )
)
